# T08-Schematic.net
KiCad netlist of a schematic drawn in EAGLE
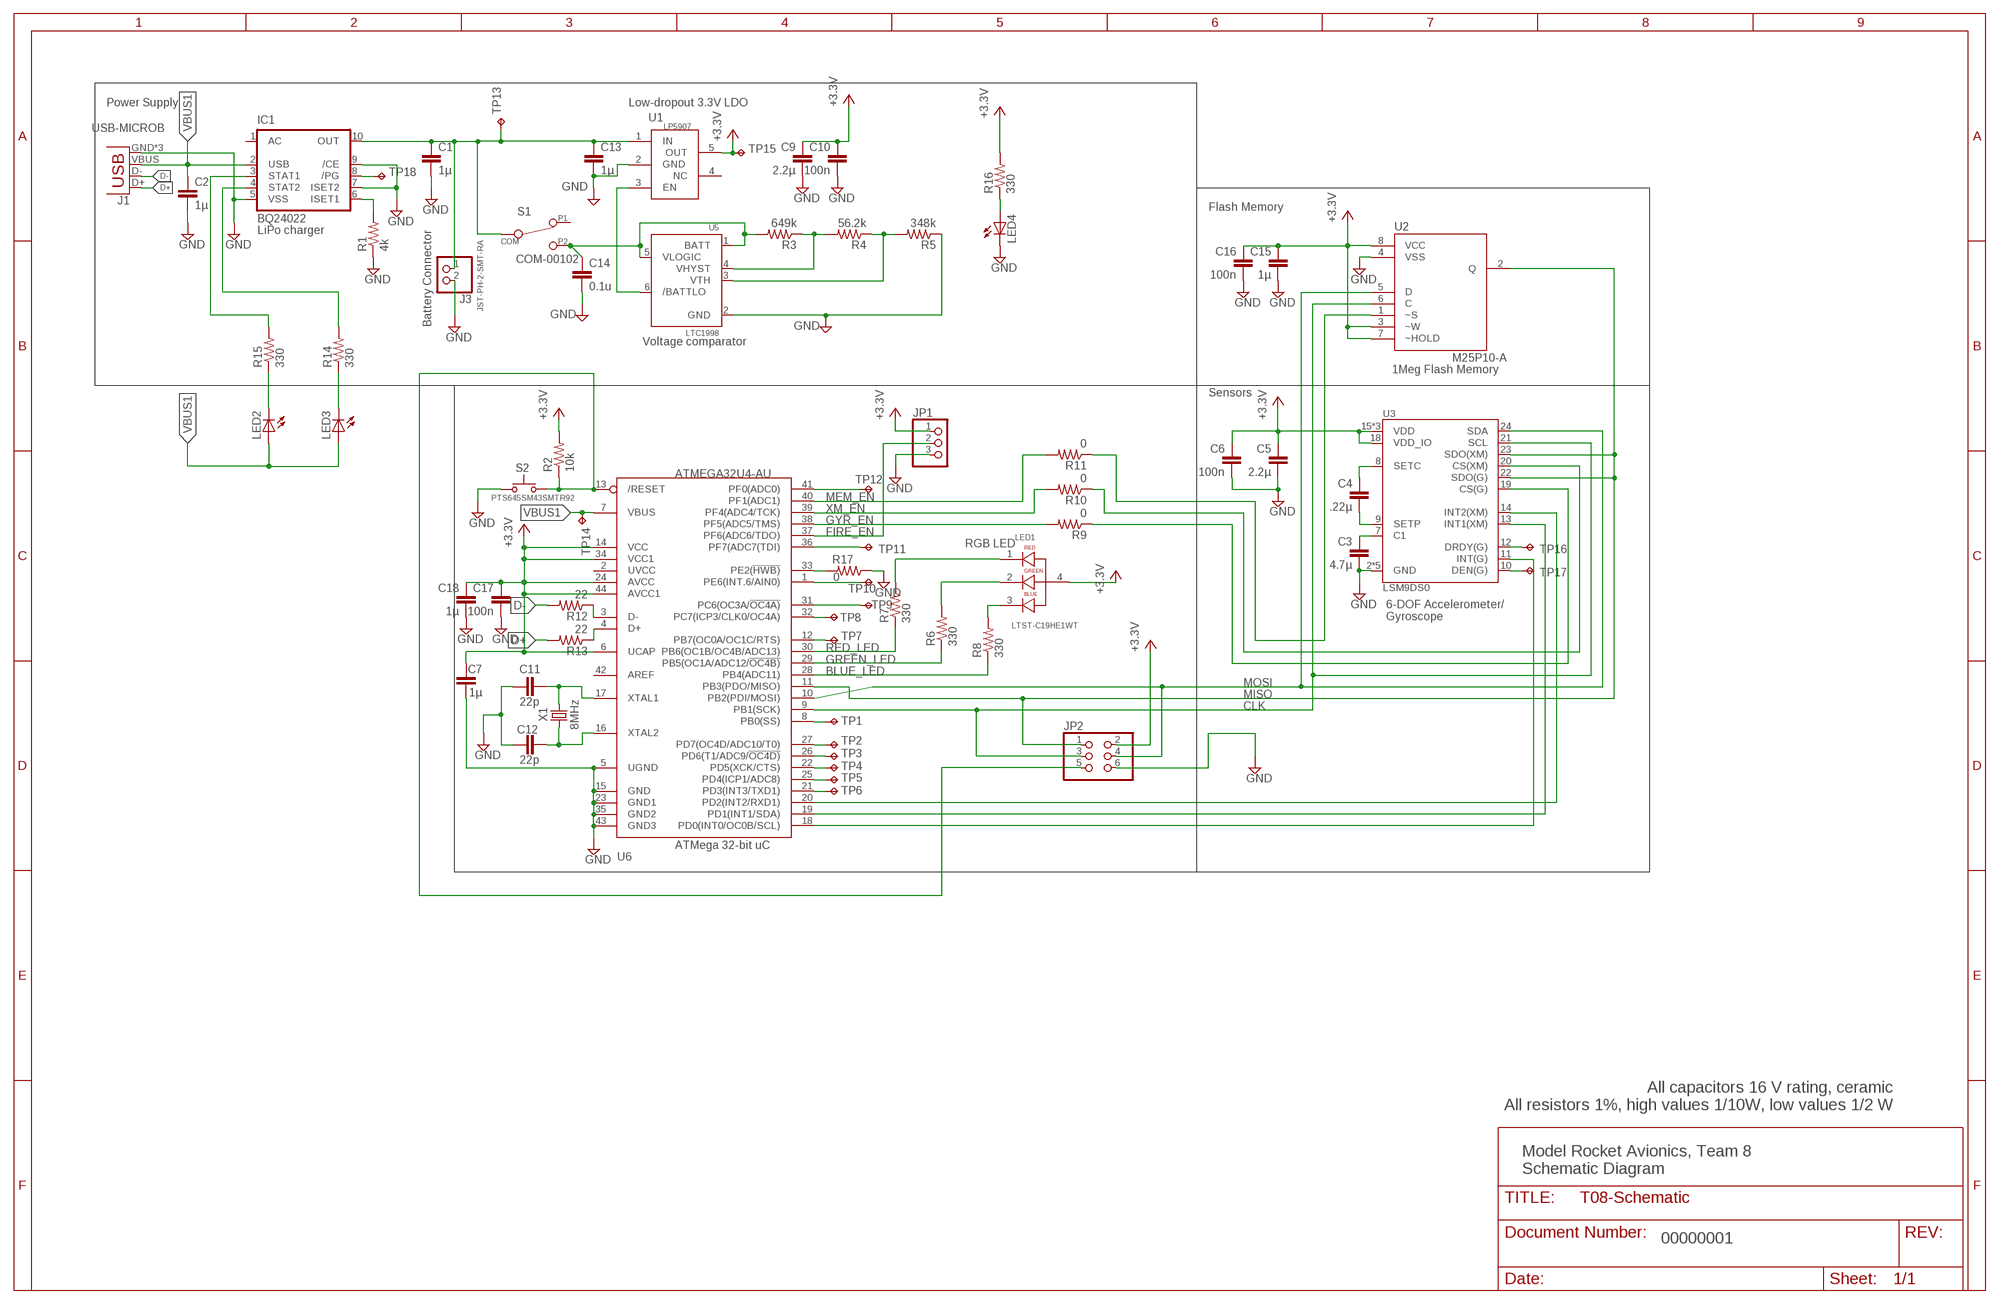
[diagram p0: schematic, sheet 1]

(export (version "E")
  (design (tool "Eeschema 10.0.6"))
  (components
    (comp (ref "C1")
      (value "1µ")
      (footprint "eagle-import:C0603")
      (libsource (lib "eagle-import") (part "C-EUC0603"))
    )
    (comp (ref "C2")
      (value "1µ")
      (footprint "eagle-import:C0805")
      (libsource (lib "eagle-import") (part "C-EUC0805"))
    )
    (comp (ref "C3")
      (value "4.7µ")
      (footprint "eagle-import:C0603")
      (libsource (lib "eagle-import") (part "C-EUC0603"))
    )
    (comp (ref "C4")
      (value ".22µ")
      (footprint "eagle-import:C0603")
      (libsource (lib "eagle-import") (part "C-EUC0603"))
    )
    (comp (ref "C5")
      (value "2.2µ")
      (footprint "eagle-import:C0603")
      (libsource (lib "eagle-import") (part "C-EUC0603"))
    )
    (comp (ref "C6")
      (value "100n")
      (footprint "eagle-import:C0603")
      (libsource (lib "eagle-import") (part "C-EUC0603"))
    )
    (comp (ref "C7")
      (value "1µ")
      (footprint "eagle-import:C0603")
      (libsource (lib "eagle-import") (part "C-EUC0603"))
    )
    (comp (ref "C9")
      (value "2.2µ")
      (footprint "eagle-import:C0603")
      (libsource (lib "eagle-import") (part "C-EUC0603"))
    )
    (comp (ref "C10")
      (value "100n")
      (footprint "eagle-import:C0603")
      (libsource (lib "eagle-import") (part "C-EUC0603"))
    )
    (comp (ref "C11")
      (value "22p")
      (footprint "eagle-import:C0603")
      (libsource (lib "eagle-import") (part "C-EUC0603"))
    )
    (comp (ref "C12")
      (value "22p")
      (footprint "eagle-import:C0603")
      (libsource (lib "eagle-import") (part "C-EUC0603"))
    )
    (comp (ref "C13")
      (value "1µ")
      (footprint "eagle-import:C0603")
      (libsource (lib "eagle-import") (part "C-EUC0603"))
    )
    (comp (ref "C14")
      (value "0.1u")
      (footprint "eagle-import:C0603")
      (libsource (lib "eagle-import") (part "C-EUC0603"))
    )
    (comp (ref "C15")
      (value "1µ")
      (footprint "eagle-import:C0603")
      (libsource (lib "eagle-import") (part "C-EUC0603"))
    )
    (comp (ref "C16")
      (value "100n")
      (footprint "eagle-import:C0603")
      (libsource (lib "eagle-import") (part "C-EUC0603"))
    )
    (comp (ref "C17")
      (value "100n")
      (footprint "eagle-import:C0603")
      (libsource (lib "eagle-import") (part "C-EUC0603"))
    )
    (comp (ref "C18")
      (value "1µ")
      (footprint "eagle-import:C0603")
      (libsource (lib "eagle-import") (part "C-EUC0603"))
    )
    (comp (ref "IC1")
      (value "BQ24022")
      (footprint "eagle-import:DRC-S-PVSON-N10")
      (libsource (lib "eagle-import") (part "BQ24022"))
    )
    (comp (ref "J1")
      (value "USB-MICROB")
      (footprint "eagle-import:USB-MICROB")
      (libsource (lib "eagle-import") (part "USB-MICROB"))
    )
    (comp (ref "J3")
      (value "JST-PH-2-SMT-RA")
      (footprint "eagle-import:JST-PH-2-SMT-RA")
      (libsource (lib "eagle-import") (part "JST_2PIN-SMT-RA"))
    )
    (comp (ref "JP1")
      (value "PINHD-1X3")
      (footprint "eagle-import:1X03")
      (libsource (lib "eagle-import") (part "PINHD-1X3"))
    )
    (comp (ref "JP2")
      (value "PINHD-2X3")
      (footprint "eagle-import:2X03")
      (libsource (lib "eagle-import") (part "PINHD-2X3"))
    )
    (comp (ref "LED1")
      (value "LTST-C19HE1WT")
      (footprint "eagle-import:LEDSC85P160X160X35-4N")
      (fields (field (name "MF") "Lite-On") (field (name "PRICE") "0.59 USD"))
      (libsource (lib "eagle-import") (part "LTST-C19HE1WT"))
    )
    (comp (ref "LED2")
      (value "LEDCHIP-LED0603")
      (footprint "eagle-import:CHIP-LED0603")
      (libsource (lib "eagle-import") (part "LEDCHIP-LED0603"))
    )
    (comp (ref "LED3")
      (value "LEDCHIP-LED0603")
      (footprint "eagle-import:CHIP-LED0603")
      (libsource (lib "eagle-import") (part "LEDCHIP-LED0603"))
    )
    (comp (ref "LED4")
      (value "LEDCHIP-LED0603")
      (footprint "eagle-import:CHIP-LED0603")
      (libsource (lib "eagle-import") (part "LEDCHIP-LED0603"))
    )
    (comp (ref "R1")
      (value "4k")
      (footprint "eagle-import:R0603")
      (libsource (lib "eagle-import") (part "R-US_R0603"))
    )
    (comp (ref "R2")
      (value "10k")
      (footprint "eagle-import:R0805")
      (libsource (lib "eagle-import") (part "R-US_R0805"))
    )
    (comp (ref "R3")
      (value "649k")
      (footprint "eagle-import:R0603")
      (libsource (lib "eagle-import") (part "R-US_R0603"))
    )
    (comp (ref "R4")
      (value "56.2k")
      (footprint "eagle-import:R0603")
      (libsource (lib "eagle-import") (part "R-US_R0603"))
    )
    (comp (ref "R5")
      (value "348k")
      (footprint "eagle-import:R0603")
      (libsource (lib "eagle-import") (part "R-US_R0603"))
    )
    (comp (ref "R6")
      (value "330")
      (footprint "eagle-import:R0805")
      (libsource (lib "eagle-import") (part "R-US_R0805"))
    )
    (comp (ref "R7")
      (value "330")
      (footprint "eagle-import:R0805")
      (libsource (lib "eagle-import") (part "R-US_R0805"))
    )
    (comp (ref "R8")
      (value "330")
      (footprint "eagle-import:R0805")
      (libsource (lib "eagle-import") (part "R-US_R0805"))
    )
    (comp (ref "R9")
      (value "0")
      (footprint "eagle-import:R0603")
      (libsource (lib "eagle-import") (part "R-US_R0603"))
    )
    (comp (ref "R10")
      (value "0")
      (footprint "eagle-import:R0603")
      (libsource (lib "eagle-import") (part "R-US_R0603"))
    )
    (comp (ref "R11")
      (value "0")
      (footprint "eagle-import:R0603")
      (libsource (lib "eagle-import") (part "R-US_R0603"))
    )
    (comp (ref "R12")
      (value "22")
      (footprint "eagle-import:R0603")
      (libsource (lib "eagle-import") (part "R-US_R0603"))
    )
    (comp (ref "R13")
      (value "22")
      (footprint "eagle-import:R0603")
      (libsource (lib "eagle-import") (part "R-US_R0603"))
    )
    (comp (ref "R14")
      (value "330")
      (footprint "eagle-import:R0805")
      (libsource (lib "eagle-import") (part "R-US_R0805"))
    )
    (comp (ref "R15")
      (value "330")
      (footprint "eagle-import:R0805")
      (libsource (lib "eagle-import") (part "R-US_R0805"))
    )
    (comp (ref "R16")
      (value "330")
      (footprint "eagle-import:R0805")
      (libsource (lib "eagle-import") (part "R-US_R0805"))
    )
    (comp (ref "R17")
      (value "0")
      (footprint "eagle-import:R0603")
      (libsource (lib "eagle-import") (part "R-US_R0603"))
    )
    (comp (ref "S1")
      (value "COM-00102")
      (footprint "eagle-import:ESWITCH")
      (libsource (lib "eagle-import") (part "COM-00102"))
    )
    (comp (ref "S2")
      (value "PTS645SM43SMTR92")
      (footprint "eagle-import:PTS645-SMD")
      (fields (field (name "MPN") "PTS645SM43SMTR92 LFS"))
      (libsource (lib "eagle-import") (part "PTS645S???SMTR"))
    )
    (comp (ref "TP1")
      (value "TPTP08R")
      (footprint "eagle-import:TP08R")
      (libsource (lib "eagle-import") (part "TPTP08R"))
    )
    (comp (ref "TP2")
      (value "TPTP08R")
      (footprint "eagle-import:TP08R")
      (libsource (lib "eagle-import") (part "TPTP08R"))
    )
    (comp (ref "TP3")
      (value "TPTP08R")
      (footprint "eagle-import:TP08R")
      (libsource (lib "eagle-import") (part "TPTP08R"))
    )
    (comp (ref "TP4")
      (value "TPTP08R")
      (footprint "eagle-import:TP08R")
      (libsource (lib "eagle-import") (part "TPTP08R"))
    )
    (comp (ref "TP5")
      (value "TPTP08R")
      (footprint "eagle-import:TP08R")
      (libsource (lib "eagle-import") (part "TPTP08R"))
    )
    (comp (ref "TP6")
      (value "TPTP08R")
      (footprint "eagle-import:TP08R")
      (libsource (lib "eagle-import") (part "TPTP08R"))
    )
    (comp (ref "TP7")
      (value "TPTP08R")
      (footprint "eagle-import:TP08R")
      (libsource (lib "eagle-import") (part "TPTP08R"))
    )
    (comp (ref "TP8")
      (value "TPTP08R")
      (footprint "eagle-import:TP08R")
      (libsource (lib "eagle-import") (part "TPTP08R"))
    )
    (comp (ref "TP9")
      (value "TPTP08R")
      (footprint "eagle-import:TP08R")
      (libsource (lib "eagle-import") (part "TPTP08R"))
    )
    (comp (ref "TP10")
      (value "TPTP08R")
      (footprint "eagle-import:TP08R")
      (libsource (lib "eagle-import") (part "TPTP08R"))
    )
    (comp (ref "TP11")
      (value "TPTP08R")
      (footprint "eagle-import:TP08R")
      (libsource (lib "eagle-import") (part "TPTP08R"))
    )
    (comp (ref "TP12")
      (value "TPTP08R")
      (footprint "eagle-import:TP08R")
      (libsource (lib "eagle-import") (part "TPTP08R"))
    )
    (comp (ref "TP13")
      (value "TPTP08R")
      (footprint "eagle-import:TP08R")
      (libsource (lib "eagle-import") (part "TPTP08R"))
    )
    (comp (ref "TP14")
      (value "TPTP08R")
      (footprint "eagle-import:TP08R")
      (libsource (lib "eagle-import") (part "TPTP08R"))
    )
    (comp (ref "TP15")
      (value "TPTP08R")
      (footprint "eagle-import:TP08R")
      (libsource (lib "eagle-import") (part "TPTP08R"))
    )
    (comp (ref "TP16")
      (value "TPTP08R")
      (footprint "eagle-import:TP08R")
      (libsource (lib "eagle-import") (part "TPTP08R"))
    )
    (comp (ref "TP17")
      (value "TPTP08R")
      (footprint "eagle-import:TP08R")
      (libsource (lib "eagle-import") (part "TPTP08R"))
    )
    (comp (ref "TP18")
      (value "TPTP08R")
      (footprint "eagle-import:TP08R")
      (libsource (lib "eagle-import") (part "TPTP08R"))
    )
    (comp (ref "U1")
      (value "LP5907")
      (footprint "eagle-import:SOT23-5L")
      (libsource (lib "eagle-import") (part "LP5907"))
    )
    (comp (ref "U2")
      (value "M25P10-AVMN6TP_TR")
      (footprint "eagle-import:SOIC127P600X175-8N")
      (libsource (lib "eagle-import") (part "M25P10-AVMN6TP_TR"))
    )
    (comp (ref "U3")
      (value "LSM9DS0")
      (footprint "eagle-import:LGA-24")
      (fields (field (name "MF") "STMicroelectronics"))
      (libsource (lib "eagle-import") (part "LSM9DS0"))
    )
    (comp (ref "U5")
      (value "LTC1998")
      (footprint "eagle-import:TSOT23-6")
      (libsource (lib "eagle-import") (part "LTC1998"))
    )
    (comp (ref "U6")
      (value "ATMEGA32U4-AU")
      (footprint "eagle-import:TQFP44")
      (libsource (lib "eagle-import") (part "ATMEGA32U4-AU"))
    )
    (comp (ref "X1")
      (value "8MHz")
      (footprint "eagle-import:HC49")
      (fields (field (name "MPN") "ATS080B"))
      (libsource (lib "eagle-import") (part "CRYSTALS-NOGND-HC49/4H"))
    )
  )
  (nets
    (net (code "1") (name "+3.3V") (class "Default")
      (node (ref "C10") (pin "1") (pinfunction "1_1") (pintype "passive"))
      (node (ref "C15") (pin "1") (pinfunction "1_1") (pintype "passive"))
      (node (ref "C16") (pin "1") (pinfunction "1_1") (pintype "passive"))
      (node (ref "C17") (pin "1") (pinfunction "1_1") (pintype "passive"))
      (node (ref "C18") (pin "1") (pinfunction "1_1") (pintype "passive"))
      (node (ref "C5") (pin "1") (pinfunction "1_1") (pintype "passive"))
      (node (ref "C6") (pin "1") (pinfunction "1_1") (pintype "passive"))
      (node (ref "C7") (pin "1") (pinfunction "1_1") (pintype "passive"))
      (node (ref "C9") (pin "1") (pinfunction "1_1") (pintype "passive"))
      (node (ref "JP1") (pin "1") (pinfunction "1_1") (pintype "passive"))
      (node (ref "JP2") (pin "2") (pinfunction "2_2") (pintype "passive"))
      (node (ref "LED1") (pin "4") (pinfunction "4_4") (pintype "passive"))
      (node (ref "R16") (pin "2") (pinfunction "2_2") (pintype "passive"))
      (node (ref "R2") (pin "2") (pinfunction "2_2") (pintype "passive"))
      (node (ref "TP15") (pin "TP") (pinfunction "TP_TP") (pintype "input"))
      (node (ref "U1") (pin "5") (pinfunction "OUT_5") (pintype "bidirectional"))
      (node (ref "U2") (pin "3") (pinfunction "~{W}_3") (pintype "bidirectional"))
      (node (ref "U2") (pin "7") (pinfunction "~{HOLD}_7") (pintype "bidirectional"))
      (node (ref "U2") (pin "8") (pinfunction "VCC_8") (pintype "bidirectional"))
      (node (ref "U3") (pin "15") (pinfunction "VDD_15") (pintype "bidirectional"))
      (node (ref "U3") (pin "16") (pinfunction "VDD_16") (pintype "bidirectional"))
      (node (ref "U3") (pin "17") (pinfunction "VDD_17") (pintype "bidirectional"))
      (node (ref "U3") (pin "18") (pinfunction "VDD_IO_18") (pintype "bidirectional"))
      (node (ref "U6") (pin "14") (pinfunction "VCC_14") (pintype "bidirectional"))
      (node (ref "U6") (pin "24") (pinfunction "AVCC_24") (pintype "bidirectional"))
      (node (ref "U6") (pin "34") (pinfunction "VCC1_34") (pintype "bidirectional"))
      (node (ref "U6") (pin "44") (pinfunction "AVCC1_44") (pintype "bidirectional"))
      (node (ref "U6") (pin "6") (pinfunction "UCAP_6") (pintype "bidirectional"))
    )
    (net (code "2") (name "/BLUE_LED") (class "Default")
      (node (ref "R8") (pin "1") (pinfunction "1_1") (pintype "passive"))
      (node (ref "U6") (pin "28") (pinfunction "PB4(ADC11)_28") (pintype "bidirectional"))
    )
    (net (code "3") (name "/CLK") (class "Default")
      (node (ref "JP2") (pin "3") (pinfunction "3_3") (pintype "passive"))
      (node (ref "U2") (pin "6") (pinfunction "C_6") (pintype "bidirectional"))
      (node (ref "U3") (pin "21") (pinfunction "SCL_21") (pintype "bidirectional"))
      (node (ref "U6") (pin "9") (pinfunction "PB1(SCK)_9") (pintype "bidirectional"))
    )
    (net (code "4") (name "/FIRE_EN") (class "Default")
      (node (ref "JP1") (pin "2") (pinfunction "2_2") (pintype "passive"))
      (node (ref "U6") (pin "37") (pinfunction "PF6(ADC6/TDO)_37") (pintype "bidirectional"))
    )
    (net (code "5") (name "/GREEN_LED") (class "Default")
      (node (ref "R6") (pin "1") (pinfunction "1_1") (pintype "passive"))
      (node (ref "U6") (pin "29") (pinfunction "PB5(OC1A/ADC12/~{OC4B})_29") (pintype "bidirectional"))
    )
    (net (code "6") (name "/GYR_EN") (class "Default")
      (node (ref "R9") (pin "1") (pinfunction "1_1") (pintype "passive"))
      (node (ref "U3") (pin "19") (pinfunction "CS(G)_19") (pintype "bidirectional"))
    )
    (net (code "7") (name "/MEM_EN") (class "Default")
      (node (ref "R11") (pin "1") (pinfunction "1_1") (pintype "passive"))
      (node (ref "U2") (pin "1") (pinfunction "~{S}_1") (pintype "bidirectional"))
    )
    (net (code "8") (name "/MISO") (class "Default")
      (node (ref "JP2") (pin "1") (pinfunction "1_1") (pintype "passive"))
      (node (ref "U2") (pin "2") (pinfunction "Q_2") (pintype "bidirectional"))
      (node (ref "U3") (pin "22") (pinfunction "SDO(G)_22") (pintype "bidirectional"))
      (node (ref "U3") (pin "23") (pinfunction "SDO(XM)_23") (pintype "bidirectional"))
      (node (ref "U6") (pin "11") (pinfunction "PB3(PDO/MISO)_11") (pintype "bidirectional"))
    )
    (net (code "9") (name "/MOSI") (class "Default")
      (node (ref "JP2") (pin "4") (pinfunction "4_4") (pintype "passive"))
      (node (ref "U2") (pin "5") (pinfunction "D_5") (pintype "bidirectional"))
      (node (ref "U3") (pin "24") (pinfunction "SDA_24") (pintype "bidirectional"))
      (node (ref "U6") (pin "10") (pinfunction "PB2(PDI/MOSI)_10") (pintype "bidirectional"))
    )
    (net (code "10") (name "/RED_LED") (class "Default")
      (node (ref "R7") (pin "1") (pinfunction "1_1") (pintype "passive"))
      (node (ref "U6") (pin "30") (pinfunction "PB6(OC1B/OC4B/ADC13)_30") (pintype "bidirectional"))
    )
    (net (code "11") (name "/XM_EN") (class "Default")
      (node (ref "R10") (pin "1") (pinfunction "1_1") (pintype "passive"))
      (node (ref "U3") (pin "20") (pinfunction "CS(XM)_20") (pintype "bidirectional"))
    )
    (net (code "12") (name "D+") (class "Default")
      (node (ref "J1") (pin "D+") (pinfunction "D+_D+") (pintype "bidirectional"))
      (node (ref "R13") (pin "2") (pinfunction "2_2") (pintype "passive"))
    )
    (net (code "13") (name "D-") (class "Default")
      (node (ref "J1") (pin "D-") (pinfunction "D-_D-") (pintype "bidirectional"))
      (node (ref "R12") (pin "2") (pinfunction "2_2") (pintype "passive"))
    )
    (net (code "14") (name "GND") (class "Default")
      (node (ref "C1") (pin "2") (pinfunction "2_2") (pintype "passive"))
      (node (ref "C10") (pin "2") (pinfunction "2_2") (pintype "passive"))
      (node (ref "C11") (pin "2") (pinfunction "2_2") (pintype "passive"))
      (node (ref "C12") (pin "2") (pinfunction "2_2") (pintype "passive"))
      (node (ref "C13") (pin "2") (pinfunction "2_2") (pintype "passive"))
      (node (ref "C14") (pin "2") (pinfunction "2_2") (pintype "passive"))
      (node (ref "C15") (pin "2") (pinfunction "2_2") (pintype "passive"))
      (node (ref "C16") (pin "2") (pinfunction "2_2") (pintype "passive"))
      (node (ref "C17") (pin "2") (pinfunction "2_2") (pintype "passive"))
      (node (ref "C18") (pin "2") (pinfunction "2_2") (pintype "passive"))
      (node (ref "C2") (pin "2") (pinfunction "2_2") (pintype "passive"))
      (node (ref "C3") (pin "1") (pinfunction "1_1") (pintype "passive"))
      (node (ref "C5") (pin "2") (pinfunction "2_2") (pintype "passive"))
      (node (ref "C6") (pin "2") (pinfunction "2_2") (pintype "passive"))
      (node (ref "C7") (pin "2") (pinfunction "2_2") (pintype "passive"))
      (node (ref "C9") (pin "2") (pinfunction "2_2") (pintype "passive"))
      (node (ref "IC1") (pin "5") (pinfunction "VSS_5") (pintype "power_in"))
      (node (ref "IC1") (pin "7") (pinfunction "ISET2_7") (pintype "input"))
      (node (ref "IC1") (pin "9") (pinfunction "/CE_9") (pintype "input"))
      (node (ref "J1") (pin "GND") (pinfunction "GND_GND") (pintype "bidirectional"))
      (node (ref "J1") (pin "MT1") (pinfunction "GND_MT1") (pintype "bidirectional"))
      (node (ref "J1") (pin "MT2") (pinfunction "GND_MT2") (pintype "bidirectional"))
      (node (ref "J3") (pin "2") (pinfunction "1_2") (pintype "passive"))
      (node (ref "JP1") (pin "3") (pinfunction "3_3") (pintype "passive"))
      (node (ref "JP2") (pin "6") (pinfunction "6_6") (pintype "passive"))
      (node (ref "LED4") (pin "C") (pinfunction "C_C") (pintype "passive"))
      (node (ref "R1") (pin "1") (pinfunction "1_1") (pintype "passive"))
      (node (ref "R17") (pin "1") (pinfunction "1_1") (pintype "passive"))
      (node (ref "R5") (pin "1") (pinfunction "1_1") (pintype "passive"))
      (node (ref "S2") (pin "1") (pinfunction "P_1") (pintype "passive"))
      (node (ref "S2") (pin "2") (pinfunction "P_2") (pintype "passive"))
      (node (ref "U1") (pin "2") (pinfunction "GND_2") (pintype "bidirectional"))
      (node (ref "U2") (pin "4") (pinfunction "VSS_4") (pintype "bidirectional"))
      (node (ref "U3") (pin "2") (pinfunction "GND_2") (pintype "bidirectional"))
      (node (ref "U3") (pin "3") (pinfunction "GND_3") (pintype "bidirectional"))
      (node (ref "U3") (pin "4") (pinfunction "GND_4") (pintype "bidirectional"))
      (node (ref "U3") (pin "5") (pinfunction "GND_5") (pintype "bidirectional"))
      (node (ref "U3") (pin "6") (pinfunction "GND_6") (pintype "bidirectional"))
      (node (ref "U5") (pin "2") (pinfunction "GND_2") (pintype "bidirectional"))
      (node (ref "U6") (pin "15") (pinfunction "GND_15") (pintype "bidirectional"))
      (node (ref "U6") (pin "23") (pinfunction "GND1_23") (pintype "bidirectional"))
      (node (ref "U6") (pin "35") (pinfunction "GND2_35") (pintype "bidirectional"))
      (node (ref "U6") (pin "43") (pinfunction "GND3_43") (pintype "bidirectional"))
      (node (ref "U6") (pin "5") (pinfunction "UGND_5") (pintype "bidirectional"))
    )
    (net (code "15") (name "Net-(IC1A-ISET1)") (class "Default")
      (node (ref "IC1") (pin "6") (pinfunction "ISET1_6") (pintype "input"))
      (node (ref "R1") (pin "2") (pinfunction "2_2") (pintype "passive"))
    )
    (net (code "16") (name "Net-(IC1A-OUT)") (class "Default")
      (node (ref "C1") (pin "1") (pinfunction "1_1") (pintype "passive"))
      (node (ref "C13") (pin "1") (pinfunction "1_1") (pintype "passive"))
      (node (ref "IC1") (pin "10") (pinfunction "OUT_10") (pintype "output"))
      (node (ref "J3") (pin "1") (pinfunction "2_1") (pintype "passive"))
      (node (ref "S1") (pin "2") (pinfunction "COM_2") (pintype "bidirectional"))
      (node (ref "TP13") (pin "TP") (pinfunction "TP_TP") (pintype "input"))
      (node (ref "U1") (pin "1") (pinfunction "IN_1") (pintype "bidirectional"))
    )
    (net (code "17") (name "Net-(IC1A-STAT1)") (class "Default")
      (node (ref "IC1") (pin "3") (pinfunction "STAT1_3") (pintype "bidirectional"))
      (node (ref "R15") (pin "2") (pinfunction "2_2") (pintype "passive"))
    )
    (net (code "18") (name "Net-(IC1A-STAT2)") (class "Default")
      (node (ref "IC1") (pin "4") (pinfunction "STAT2_4") (pintype "bidirectional"))
      (node (ref "R14") (pin "2") (pinfunction "2_2") (pintype "passive"))
    )
    (net (code "19") (name "Net-(IC1A-{slash}PG)") (class "Default")
      (node (ref "IC1") (pin "8") (pinfunction "/PG_8") (pintype "output"))
      (node (ref "TP18") (pin "TP") (pinfunction "TP_TP") (pintype "input"))
    )
    (net (code "20") (name "Net-(LED1-Pad1)") (class "Default")
      (node (ref "LED1") (pin "1") (pinfunction "1_1") (pintype "passive"))
      (node (ref "R7") (pin "2") (pinfunction "2_2") (pintype "passive"))
    )
    (net (code "21") (name "Net-(LED1-Pad2)") (class "Default")
      (node (ref "LED1") (pin "2") (pinfunction "2_2") (pintype "passive"))
      (node (ref "R6") (pin "2") (pinfunction "2_2") (pintype "passive"))
    )
    (net (code "22") (name "Net-(LED1-Pad3)") (class "Default")
      (node (ref "LED1") (pin "3") (pinfunction "3_3") (pintype "passive"))
      (node (ref "R8") (pin "2") (pinfunction "2_2") (pintype "passive"))
    )
    (net (code "23") (name "Net-(LED2-PadC)") (class "Default")
      (node (ref "LED2") (pin "C") (pinfunction "C_C") (pintype "passive"))
      (node (ref "R15") (pin "1") (pinfunction "1_1") (pintype "passive"))
    )
    (net (code "24") (name "Net-(LED3-PadC)") (class "Default")
      (node (ref "LED3") (pin "C") (pinfunction "C_C") (pintype "passive"))
      (node (ref "R14") (pin "1") (pinfunction "1_1") (pintype "passive"))
    )
    (net (code "25") (name "Net-(LED4-PadA)") (class "Default")
      (node (ref "LED4") (pin "A") (pinfunction "A_A") (pintype "passive"))
      (node (ref "R16") (pin "1") (pinfunction "1_1") (pintype "passive"))
    )
    (net (code "26") (name "Net-(S1-P2)") (class "Default")
      (node (ref "C14") (pin "1") (pinfunction "1_1") (pintype "passive"))
      (node (ref "R3") (pin "2") (pinfunction "2_2") (pintype "passive"))
      (node (ref "S1") (pin "3") (pinfunction "P2_3") (pintype "bidirectional"))
      (node (ref "U5") (pin "1") (pinfunction "BATT_1") (pintype "bidirectional"))
      (node (ref "U5") (pin "5") (pinfunction "VLOGIC_5") (pintype "bidirectional"))
    )
    (net (code "27") (name "Net-(U1-EN)") (class "Default")
      (node (ref "U1") (pin "3") (pinfunction "EN_3") (pintype "bidirectional"))
      (node (ref "U5") (pin "6") (pinfunction "/BATTLO_6") (pintype "bidirectional"))
    )
    (net (code "28") (name "Net-(U3-C1)") (class "Default")
      (node (ref "C3") (pin "2") (pinfunction "2_2") (pintype "passive"))
      (node (ref "U3") (pin "7") (pinfunction "C1_7") (pintype "bidirectional"))
    )
    (net (code "29") (name "Net-(U3-DEN(G))") (class "Default")
      (node (ref "TP17") (pin "TP") (pinfunction "TP_TP") (pintype "input"))
      (node (ref "U3") (pin "10") (pinfunction "DEN(G)_10") (pintype "bidirectional"))
    )
    (net (code "30") (name "Net-(U3-DRDY(G))") (class "Default")
      (node (ref "TP16") (pin "TP") (pinfunction "TP_TP") (pintype "input"))
      (node (ref "U3") (pin "12") (pinfunction "DRDY(G)_12") (pintype "bidirectional"))
    )
    (net (code "31") (name "Net-(U3-INT(G))") (class "Default")
      (node (ref "U3") (pin "11") (pinfunction "INT(G)_11") (pintype "bidirectional"))
      (node (ref "U6") (pin "18") (pinfunction "PD0(INT0/OC0B/SCL)_18") (pintype "bidirectional"))
    )
    (net (code "32") (name "Net-(U3-INT1(XM))") (class "Default")
      (node (ref "U3") (pin "13") (pinfunction "INT1(XM)_13") (pintype "bidirectional"))
      (node (ref "U6") (pin "19") (pinfunction "PD1(INT1/SDA)_19") (pintype "bidirectional"))
    )
    (net (code "33") (name "Net-(U3-INT2(XM))") (class "Default")
      (node (ref "U3") (pin "14") (pinfunction "INT2(XM)_14") (pintype "bidirectional"))
      (node (ref "U6") (pin "20") (pinfunction "PD2(INT2/RXD1)_20") (pintype "bidirectional"))
    )
    (net (code "34") (name "Net-(U3-SETC)") (class "Default")
      (node (ref "C4") (pin "2") (pinfunction "2_2") (pintype "passive"))
      (node (ref "U3") (pin "8") (pinfunction "SETC_8") (pintype "bidirectional"))
    )
    (net (code "35") (name "Net-(U3-SETP)") (class "Default")
      (node (ref "C4") (pin "1") (pinfunction "1_1") (pintype "passive"))
      (node (ref "U3") (pin "9") (pinfunction "SETP_9") (pintype "bidirectional"))
    )
    (net (code "36") (name "Net-(U5-VHYST)") (class "Default")
      (node (ref "R3") (pin "1") (pinfunction "1_1") (pintype "passive"))
      (node (ref "R4") (pin "2") (pinfunction "2_2") (pintype "passive"))
      (node (ref "U5") (pin "4") (pinfunction "VHYST_4") (pintype "bidirectional"))
    )
    (net (code "37") (name "Net-(U5-VTH)") (class "Default")
      (node (ref "R4") (pin "1") (pinfunction "1_1") (pintype "passive"))
      (node (ref "R5") (pin "2") (pinfunction "2_2") (pintype "passive"))
      (node (ref "U5") (pin "3") (pinfunction "VTH_3") (pintype "bidirectional"))
    )
    (net (code "38") (name "Net-(U6-D+)") (class "Default")
      (node (ref "R13") (pin "1") (pinfunction "1_1") (pintype "passive"))
      (node (ref "U6") (pin "4") (pinfunction "D+_4") (pintype "bidirectional"))
    )
    (net (code "39") (name "Net-(U6-D-)") (class "Default")
      (node (ref "R12") (pin "1") (pinfunction "1_1") (pintype "passive"))
      (node (ref "U6") (pin "3") (pinfunction "D-_3") (pintype "bidirectional"))
    )
    (net (code "40") (name "Net-(U6-PB0(SS))") (class "Default")
      (node (ref "TP1") (pin "TP") (pinfunction "TP_TP") (pintype "input"))
      (node (ref "U6") (pin "8") (pinfunction "PB0(SS)_8") (pintype "bidirectional"))
    )
    (net (code "41") (name "Net-(U6-PB7(OC0A{slash}OC1C{slash}RTS))") (class "Default")
      (node (ref "TP7") (pin "TP") (pinfunction "TP_TP") (pintype "input"))
      (node (ref "U6") (pin "12") (pinfunction "PB7(OC0A/OC1C/RTS)_12") (pintype "bidirectional"))
    )
    (net (code "42") (name "Net-(U6-PC6(OC3A{slash}~{OC4A}))") (class "Default")
      (node (ref "TP9") (pin "TP") (pinfunction "TP_TP") (pintype "input"))
      (node (ref "U6") (pin "31") (pinfunction "PC6(OC3A/~{OC4A})_31") (pintype "bidirectional"))
    )
    (net (code "43") (name "Net-(U6-PC7(ICP3{slash}CLK0{slash}OC4A))") (class "Default")
      (node (ref "TP8") (pin "TP") (pinfunction "TP_TP") (pintype "input"))
      (node (ref "U6") (pin "32") (pinfunction "PC7(ICP3/CLK0/OC4A)_32") (pintype "bidirectional"))
    )
    (net (code "44") (name "Net-(U6-PD3(INT3{slash}TXD1))") (class "Default")
      (node (ref "TP6") (pin "TP") (pinfunction "TP_TP") (pintype "input"))
      (node (ref "U6") (pin "21") (pinfunction "PD3(INT3/TXD1)_21") (pintype "bidirectional"))
    )
    (net (code "45") (name "Net-(U6-PD4(ICP1{slash}ADC8))") (class "Default")
      (node (ref "TP5") (pin "TP") (pinfunction "TP_TP") (pintype "input"))
      (node (ref "U6") (pin "25") (pinfunction "PD4(ICP1/ADC8)_25") (pintype "bidirectional"))
    )
    (net (code "46") (name "Net-(U6-PD5(XCK{slash}CTS))") (class "Default")
      (node (ref "TP4") (pin "TP") (pinfunction "TP_TP") (pintype "input"))
      (node (ref "U6") (pin "22") (pinfunction "PD5(XCK/CTS)_22") (pintype "bidirectional"))
    )
    (net (code "47") (name "Net-(U6-PD6(T1{slash}ADC9{slash}~{OC4D}))") (class "Default")
      (node (ref "TP3") (pin "TP") (pinfunction "TP_TP") (pintype "input"))
      (node (ref "U6") (pin "26") (pinfunction "PD6(T1/ADC9/~{OC4D})_26") (pintype "bidirectional"))
    )
    (net (code "48") (name "Net-(U6-PD7(OC4D{slash}ADC10{slash}T0))") (class "Default")
      (node (ref "TP2") (pin "TP") (pinfunction "TP_TP") (pintype "input"))
      (node (ref "U6") (pin "27") (pinfunction "PD7(OC4D/ADC10/T0)_27") (pintype "bidirectional"))
    )
    (net (code "49") (name "Net-(U6-PE2(~{HWB}))") (class "Default")
      (node (ref "R17") (pin "2") (pinfunction "2_2") (pintype "passive"))
      (node (ref "U6") (pin "33") (pinfunction "PE2(~{HWB})_33") (pintype "bidirectional"))
    )
    (net (code "50") (name "Net-(U6-PE6(INT.6{slash}AIN0))") (class "Default")
      (node (ref "TP10") (pin "TP") (pinfunction "TP_TP") (pintype "input"))
      (node (ref "U6") (pin "1") (pinfunction "PE6(INT.6/AIN0)_1") (pintype "bidirectional"))
    )
    (net (code "51") (name "Net-(U6-PF0(ADC0))") (class "Default")
      (node (ref "TP12") (pin "TP") (pinfunction "TP_TP") (pintype "input"))
      (node (ref "U6") (pin "41") (pinfunction "PF0(ADC0)_41") (pintype "bidirectional"))
    )
    (net (code "52") (name "Net-(U6-PF1(ADC1))") (class "Default")
      (node (ref "R11") (pin "2") (pinfunction "2_2") (pintype "passive"))
      (node (ref "U6") (pin "40") (pinfunction "PF1(ADC1)_40") (pintype "bidirectional"))
    )
    (net (code "53") (name "Net-(U6-PF4(ADC4{slash}TCK))") (class "Default")
      (node (ref "R10") (pin "2") (pinfunction "2_2") (pintype "passive"))
      (node (ref "U6") (pin "39") (pinfunction "PF4(ADC4/TCK)_39") (pintype "bidirectional"))
    )
    (net (code "54") (name "Net-(U6-PF5(ADC5{slash}TMS))") (class "Default")
      (node (ref "R9") (pin "2") (pinfunction "2_2") (pintype "passive"))
      (node (ref "U6") (pin "38") (pinfunction "PF5(ADC5/TMS)_38") (pintype "bidirectional"))
    )
    (net (code "55") (name "Net-(U6-PF7(ADC7(TDI))") (class "Default")
      (node (ref "TP11") (pin "TP") (pinfunction "TP_TP") (pintype "input"))
      (node (ref "U6") (pin "36") (pinfunction "PF7(ADC7(TDI)_36") (pintype "bidirectional"))
    )
    (net (code "56") (name "Net-(U6-XTAL1)") (class "Default")
      (node (ref "C11") (pin "1") (pinfunction "1_1") (pintype "passive"))
      (node (ref "U6") (pin "17") (pinfunction "XTAL1_17") (pintype "bidirectional"))
      (node (ref "X1") (pin "1") (pinfunction "1_1") (pintype "passive"))
    )
    (net (code "57") (name "Net-(U6-XTAL2)") (class "Default")
      (node (ref "C12") (pin "1") (pinfunction "1_1") (pintype "passive"))
      (node (ref "U6") (pin "16") (pinfunction "XTAL2_16") (pintype "bidirectional"))
      (node (ref "X1") (pin "2") (pinfunction "2_2") (pintype "passive"))
    )
    (net (code "58") (name "Net-(U6-{slash}RESET)") (class "Default")
      (node (ref "JP2") (pin "5") (pinfunction "5_5") (pintype "passive"))
      (node (ref "R2") (pin "1") (pinfunction "1_1") (pintype "passive"))
      (node (ref "S2") (pin "3") (pinfunction "S_3") (pintype "passive"))
      (node (ref "S2") (pin "4") (pinfunction "S_4") (pintype "passive"))
      (node (ref "U6") (pin "13") (pinfunction "/RESET_13") (pintype "bidirectional"))
    )
    (net (code "59") (name "VBUS1") (class "Default")
      (node (ref "C2") (pin "1") (pinfunction "1_1") (pintype "passive"))
      (node (ref "IC1") (pin "2") (pinfunction "USB_2") (pintype "bidirectional"))
      (node (ref "J1") (pin "VBUS") (pinfunction "VBUS_VBUS") (pintype "bidirectional"))
      (node (ref "LED2") (pin "A") (pinfunction "A_A") (pintype "passive"))
      (node (ref "LED3") (pin "A") (pinfunction "A_A") (pintype "passive"))
      (node (ref "TP14") (pin "TP") (pinfunction "TP_TP") (pintype "input"))
      (node (ref "U6") (pin "7") (pinfunction "VBUS_7") (pintype "bidirectional"))
    )
    (net (code "60") (name "unconnected-(IC1A-AC-Pad1)") (class "Default")
      (node (ref "IC1") (pin "1") (pinfunction "AC_1") (pintype "input"))
    )
    (net (code "61") (name "unconnected-(S1-P1-Pad1)") (class "Default")
      (node (ref "S1") (pin "1") (pinfunction "P1_1") (pintype "bidirectional"))
    )
    (net (code "62") (name "unconnected-(U1-NC-Pad4)") (class "Default")
      (node (ref "U1") (pin "4") (pinfunction "NC_4") (pintype "bidirectional"))
    )
    (net (code "63") (name "unconnected-(U6-AREF-Pad42)") (class "Default")
      (node (ref "U6") (pin "42") (pinfunction "AREF_42") (pintype "bidirectional"))
    )
    (net (code "64") (name "unconnected-(U6-UVCC-Pad2)") (class "Default")
      (node (ref "U6") (pin "2") (pinfunction "UVCC_2") (pintype "bidirectional"))
    )
  )
)
